# dsPIC.net
KiCad netlist of a schematic drawn in Altium Designer
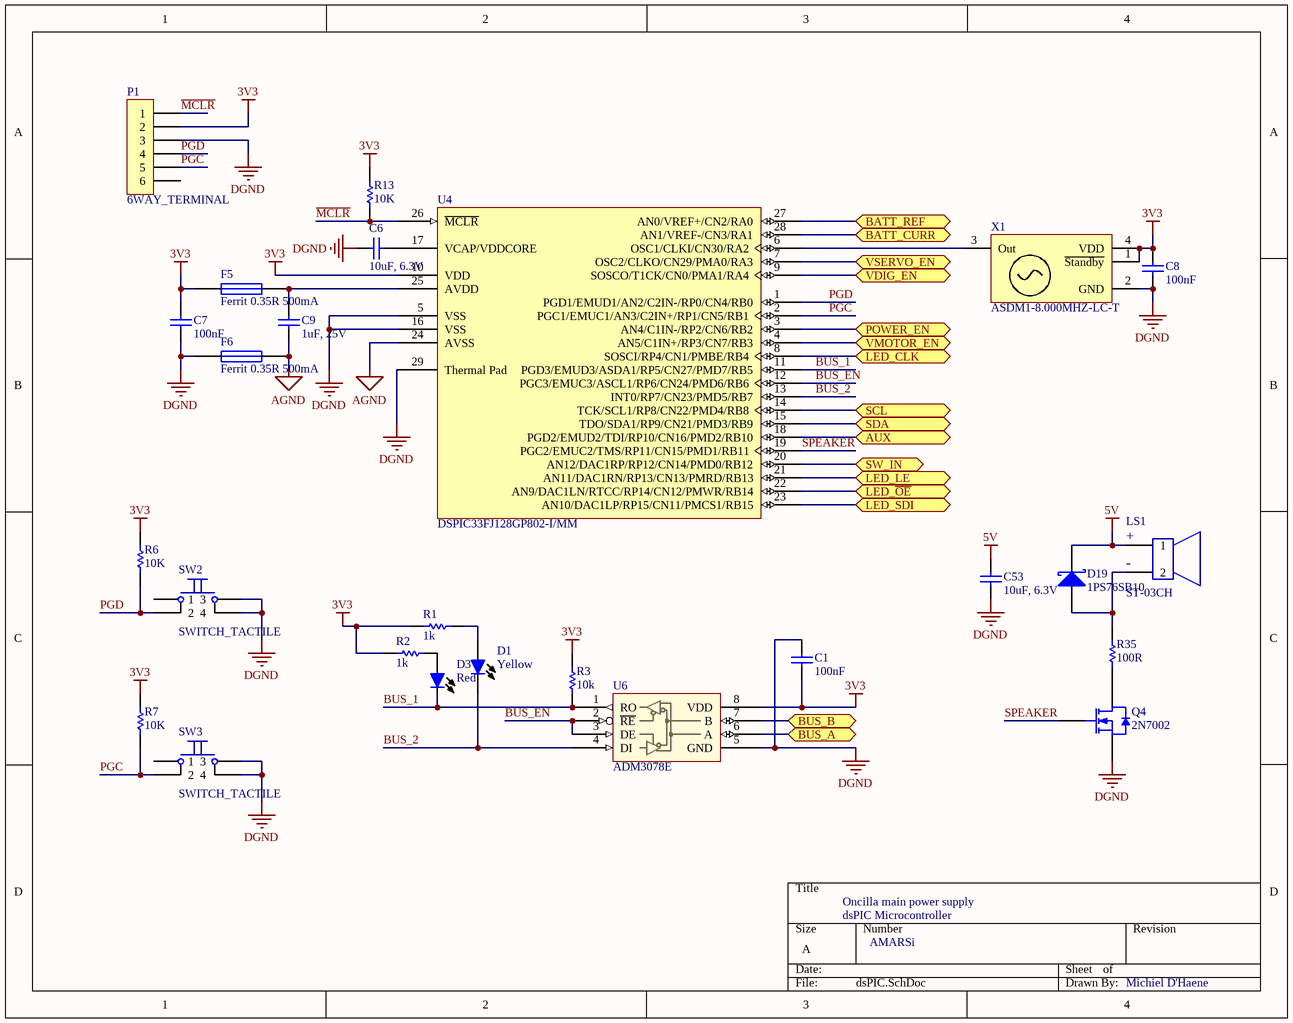
[diagram p0: dsPIC.SchDoc]

(export (version "E")
  (design (tool "Eeschema 10.0.6"))
  (components
    (comp (ref "C1")
      (value "100nF")
      (footprint "CAPC1608L")
      (description "Capacitor (Semiconductor SIM Model)")
      (fields (field (name "PUBLISHER") "Altium Limited"))
      (libsource (lib "Miscellaneous Devices") (part "Cap Semi"))
    )
    (comp (ref "C6")
      (value "10uF, 6.3V")
      (footprint "CAPC1608L")
      (description "Capacitor (Semiconductor SIM Model)")
      (fields (field (name "PUBLISHER") "Altium Limited"))
      (libsource (lib "Miscellaneous Devices") (part "Cap Semi"))
    )
    (comp (ref "C7")
      (value "100nF")
      (footprint "CAPC1608L")
      (description "Capacitor (Semiconductor SIM Model)")
      (fields (field (name "PUBLISHER") "Altium Limited"))
      (libsource (lib "Miscellaneous Devices") (part "Cap Semi"))
    )
    (comp (ref "C8")
      (value "100nF")
      (footprint "CAPC1608L")
      (description "Capacitor (Semiconductor SIM Model)")
      (fields (field (name "PUBLISHER") "Altium Limited"))
      (libsource (lib "Miscellaneous Devices") (part "Cap Semi"))
    )
    (comp (ref "C9")
      (value "1uF, 25V")
      (footprint "CAPC1608L")
      (description "Capacitor (Semiconductor SIM Model)")
      (fields (field (name "PUBLISHER") "Altium Limited"))
      (libsource (lib "Miscellaneous Devices") (part "Cap Semi"))
    )
    (comp (ref "C53")
      (value "10uF, 6.3V")
      (footprint "CAPC1608L")
      (description "Capacitor (Semiconductor SIM Model)")
      (fields (field (name "Comment") "1uF, 25V") (field (name "PUBLISHER") "Altium Limited"))
      (libsource (lib "Miscellaneous Devices") (part "Cap Semi"))
    )
    (comp (ref "D1")
      (value "LED Yellow")
      (footprint "CD1608-0603")
      (description "LED")
      (fields (field (name "COLOR") "Yellow"))
      (libsource (lib "Roombots") (part "LED"))
    )
    (comp (ref "D3")
      (value "LED Red")
      (footprint "CD1608-0603")
      (description "LED")
      (fields (field (name "COLOR") "Red"))
      (libsource (lib "Roombots") (part "LED"))
    )
    (comp (ref "D19")
      (value "1PS76SB10")
      (footprint "SOD323")
      (description "Schottky Barrier Diode")
      (fields (field (name "PUBLISHER") "Altium Limited"))
      (libsource (lib "Philips Discrete Diode - Schottky") (part "1PS76SB10"))
    )
    (comp (ref "F5")
      (value "Ferrit 0.35R 500mA")
      (footprint "RESC1608L")
      (description "Ferrit Bead")
      (fields (field (name "PUBLISHER") "Altium Limited"))
      (libsource (lib "Miscellaneous Devices") (part "Fuse 1"))
    )
    (comp (ref "F6")
      (value "Ferrit 0.35R 500mA")
      (footprint "RESC1608L")
      (description "Ferrit Bead")
      (fields (field (name "PUBLISHER") "Altium Limited"))
      (libsource (lib "Miscellaneous Devices") (part "Fuse 1"))
    )
    (comp (ref "LS1")
      (value "ST-03CH")
      (footprint "PIEZO_8.5x8.5MM")
      (libsource (lib "New_library") (part "piezo_sounder"))
    )
    (comp (ref "P1")
      (value "6WAY_TERMINAL")
      (footprint "MICROMATCH_6WAY_SE")
      (libsource (lib "New_library") (part "6WAY_TERMINAL"))
    )
    (comp (ref "Q4")
      (value "2N7002")
      (footprint "SOT23_N")
      (description "N-channel Enhancement Mode Field-effect Transistor")
      (fields (field (name "PUBLISHER") "Altium Limited"))
      (libsource (lib "Philips Discrete MOSFET - Low Power") (part "BST82"))
    )
    (comp (ref "R1")
      (value "1k")
      (footprint "RESC1608L")
      (description "Semiconductor Resistor")
      (fields (field (name "PUBLISHER") "Altium Limited"))
      (libsource (lib "Miscellaneous Devices") (part "Res Semi"))
    )
    (comp (ref "R2")
      (value "1k")
      (footprint "RESC1608L")
      (description "Semiconductor Resistor")
      (fields (field (name "PUBLISHER") "Altium Limited"))
      (libsource (lib "Miscellaneous Devices") (part "Res Semi"))
    )
    (comp (ref "R3")
      (value "10k")
      (footprint "RESC1608L")
      (description "Semiconductor Resistor")
      (fields (field (name "PUBLISHER") "Altium Limited"))
      (libsource (lib "Miscellaneous Devices") (part "Res Semi"))
    )
    (comp (ref "R6")
      (value "10K")
      (footprint "RESC1608L")
      (description "Semiconductor Resistor")
      (fields (field (name "Comment") "10k") (field (name "PUBLISHER") "Altium Limited"))
      (libsource (lib "Miscellaneous Devices") (part "Res Semi"))
    )
    (comp (ref "R7")
      (value "10K")
      (footprint "RESC1608L")
      (description "Semiconductor Resistor")
      (fields (field (name "Comment") "10k") (field (name "PUBLISHER") "Altium Limited"))
      (libsource (lib "Miscellaneous Devices") (part "Res Semi"))
    )
    (comp (ref "R13")
      (value "10K")
      (footprint "RESC1608L")
      (description "Semiconductor Resistor")
      (fields (field (name "Comment") "10k") (field (name "PUBLISHER") "Altium Limited"))
      (libsource (lib "Miscellaneous Devices") (part "Res Semi"))
    )
    (comp (ref "R35")
      (value "100R")
      (footprint "RESC2012L")
      (description "Semiconductor Resistor")
      (fields (field (name "PUBLISHER") "Altium Limited"))
      (libsource (lib "Miscellaneous Devices") (part "Res Semi"))
    )
    (comp (ref "SW2")
      (value "SWITCH_TACTILE")
      (footprint "TACTILE_SWITCH")
      (libsource (lib "New_library") (part "SWITCH_TACTILE"))
    )
    (comp (ref "SW3")
      (value "SWITCH_TACTILE")
      (footprint "TACTILE_SWITCH")
      (libsource (lib "New_library") (part "SWITCH_TACTILE"))
    )
    (comp (ref "U4")
      (value "DSPIC33FJ128GP802-I/MM")
      (footprint "QFNS-MM28_N")
      (fields (field (name "PUBLISHER") "Altium Limited"))
      (libsource (lib "Microchip DSC 16-Bit dsPIC33F") (part "DSPIC33FJ128GP802T-I/MM"))
    )
    (comp (ref "U6")
      (value "ADM3078E")
      (footprint "SOIC-8_M")
      (description "Half-Duplex RS485 Transciever, 3.3V, 16Mbps")
      (libsource (lib "Roombots") (part "ADM3078E"))
    )
    (comp (ref "X1")
      (value "ASDM1-8.000MHZ-LC-T")
      (footprint "Crystal-Oscillator-2520")
      (description "Oscillator")
      (libsource (lib "Roombots") (part "Oscillator"))
    )
  )
  (nets
    (net (code "1") (name "/AUX") (class "Default")
      (node (ref "U4") (pin "18") (pinfunction "PGD2/EMUD2/TDI/RP10/CN16/PMD2/RB10_18") (pintype "bidirectional"))
    )
    (net (code "2") (name "/BATT_CURR") (class "Default")
      (node (ref "U4") (pin "28") (pinfunction "AN1/VREF-/CN3/RA1_28") (pintype "bidirectional"))
    )
    (net (code "3") (name "/BATT_REF") (class "Default")
      (node (ref "U4") (pin "27") (pinfunction "AN0/VREF+/CN2/RA0_27") (pintype "bidirectional"))
    )
    (net (code "4") (name "/BUS_1") (class "Default")
      (node (ref "D3") (pin "2") (pinfunction "C_2") (pintype "passive"))
      (node (ref "R3") (pin "1") (pinfunction "1_1") (pintype "passive"))
      (node (ref "U4") (pin "11") (pinfunction "PGD3/EMUD3/ASDA1/RP5/CN27/PMD7/RB5_11") (pintype "bidirectional"))
      (node (ref "U6") (pin "1") (pinfunction "RO_1") (pintype "output"))
    )
    (net (code "5") (name "/BUS_2") (class "Default")
      (node (ref "D1") (pin "2") (pinfunction "C_2") (pintype "passive"))
      (node (ref "U4") (pin "13") (pinfunction "INT0/RP7/CN23/PMD5/RB7_13") (pintype "bidirectional"))
      (node (ref "U6") (pin "4") (pinfunction "DI_4") (pintype "input"))
    )
    (net (code "6") (name "/BUS_A") (class "Default")
      (node (ref "U6") (pin "6") (pinfunction "A_6") (pintype "bidirectional"))
    )
    (net (code "7") (name "/BUS_B") (class "Default")
      (node (ref "U6") (pin "7") (pinfunction "B_7") (pintype "bidirectional"))
    )
    (net (code "8") (name "/BUS_EN") (class "Default")
      (node (ref "U4") (pin "12") (pinfunction "PGC3/EMUC3/ASCL1/RP6/CN24/PMD6/RB6_12") (pintype "bidirectional"))
      (node (ref "U6") (pin "2") (pinfunction "~{RE}_2") (pintype "input"))
      (node (ref "U6") (pin "3") (pinfunction "DE_3") (pintype "input"))
    )
    (net (code "9") (name "/LED_CLK") (class "Default")
      (node (ref "U4") (pin "8") (pinfunction "SOSCI/RP4/CN1/PMBE/RB4_8") (pintype "bidirectional"))
    )
    (net (code "10") (name "/LED_LE") (class "Default")
      (node (ref "U4") (pin "21") (pinfunction "AN11/DAC1RN/RP13/CN13/PMRD/RB13_21") (pintype "bidirectional"))
    )
    (net (code "11") (name "/LED_SDI") (class "Default")
      (node (ref "U4") (pin "23") (pinfunction "AN10/DAC1LP/RP15/CN11/PMCS1/RB15_23") (pintype "bidirectional"))
    )
    (net (code "12") (name "/LED_~{OE}") (class "Default")
      (node (ref "U4") (pin "22") (pinfunction "AN9/DAC1LN/RTCC/RP14/CN12/PMWR/RB14_22") (pintype "bidirectional"))
    )
    (net (code "13") (name "/PGC") (class "Default")
      (node (ref "P1") (pin "5") (pinfunction "5_5") (pintype "passive"))
      (node (ref "R7") (pin "1") (pinfunction "1_1") (pintype "passive"))
      (node (ref "SW3") (pin "2") (pinfunction "2_2") (pintype "passive"))
      (node (ref "U4") (pin "2") (pinfunction "PGC1/EMUC1/AN3/C2IN+/RP1/CN5/RB1_2") (pintype "bidirectional"))
    )
    (net (code "14") (name "/PGD") (class "Default")
      (node (ref "P1") (pin "4") (pinfunction "4_4") (pintype "passive"))
      (node (ref "R6") (pin "1") (pinfunction "1_1") (pintype "passive"))
      (node (ref "SW2") (pin "2") (pinfunction "2_2") (pintype "passive"))
      (node (ref "U4") (pin "1") (pinfunction "PGD1/EMUD1/AN2/C2IN-/RP0/CN4/RB0_1") (pintype "bidirectional"))
    )
    (net (code "15") (name "/POWER_EN") (class "Default")
      (node (ref "U4") (pin "3") (pinfunction "AN4/C1IN-/RP2/CN6/RB2_3") (pintype "bidirectional"))
    )
    (net (code "16") (name "/SCL") (class "Default")
      (node (ref "U4") (pin "14") (pinfunction "TCK/SCL1/RP8/CN22/PMD4/RB8_14") (pintype "bidirectional"))
    )
    (net (code "17") (name "/SDA") (class "Default")
      (node (ref "U4") (pin "15") (pinfunction "TDO/SDA1/RP9/CN21/PMD3/RB9_15") (pintype "bidirectional"))
    )
    (net (code "18") (name "/SPEAKER") (class "Default")
      (node (ref "Q4") (pin "1") (pinfunction "G_1") (pintype "passive"))
      (node (ref "U4") (pin "19") (pinfunction "PGC2/EMUC2/TMS/RP11/CN15/PMD1/RB11_19") (pintype "bidirectional"))
    )
    (net (code "19") (name "/SW_IN") (class "Default")
      (node (ref "U4") (pin "20") (pinfunction "AN12/DAC1RP/RP12/CN14/PMD0/RB12_20") (pintype "bidirectional"))
    )
    (net (code "20") (name "/VDIG_EN") (class "Default")
      (node (ref "U4") (pin "9") (pinfunction "SOSCO/T1CK/CN0/PMA1/RA4_9") (pintype "bidirectional"))
    )
    (net (code "21") (name "/VMOTOR_EN") (class "Default")
      (node (ref "U4") (pin "4") (pinfunction "AN5/C1IN+/RP3/CN7/RB3_4") (pintype "bidirectional"))
    )
    (net (code "22") (name "/VSERVO_EN") (class "Default")
      (node (ref "U4") (pin "7") (pinfunction "OSC2/CLKO/CN29/PMA0/RA3_7") (pintype "bidirectional"))
    )
    (net (code "23") (name "/~{MCLR}") (class "Default")
      (node (ref "P1") (pin "1") (pinfunction "1_1") (pintype "passive"))
      (node (ref "R13") (pin "1") (pinfunction "1_1") (pintype "passive"))
      (node (ref "U4") (pin "26") (pinfunction "~{MCLR}_26") (pintype "input"))
    )
    (net (code "24") (name "3V3") (class "Default")
      (node (ref "C1") (pin "1") (pinfunction "1_1") (pintype "passive"))
      (node (ref "C7") (pin "2") (pinfunction "2_2") (pintype "passive"))
      (node (ref "C8") (pin "2") (pinfunction "2_2") (pintype "passive"))
      (node (ref "F5") (pin "1") (pinfunction "1_1") (pintype "passive"))
      (node (ref "P1") (pin "2") (pinfunction "2_2") (pintype "passive"))
      (node (ref "R1") (pin "1") (pinfunction "1_1") (pintype "passive"))
      (node (ref "R13") (pin "2") (pinfunction "2_2") (pintype "passive"))
      (node (ref "R2") (pin "1") (pinfunction "1_1") (pintype "passive"))
      (node (ref "R3") (pin "2") (pinfunction "2_2") (pintype "passive"))
      (node (ref "R6") (pin "2") (pinfunction "2_2") (pintype "passive"))
      (node (ref "R7") (pin "2") (pinfunction "2_2") (pintype "passive"))
      (node (ref "U4") (pin "10") (pinfunction "VDD_10") (pintype "power_in"))
      (node (ref "U6") (pin "8") (pinfunction "VDD_8") (pintype "power_in"))
      (node (ref "X1") (pin "1") (pinfunction "~{Standby}_1") (pintype "passive"))
      (node (ref "X1") (pin "4") (pinfunction "VDD_4") (pintype "passive"))
    )
    (net (code "25") (name "5V") (class "Default")
      (node (ref "C53") (pin "1") (pinfunction "1_1") (pintype "passive"))
      (node (ref "D19") (pin "1") (pinfunction "K_1") (pintype "passive"))
      (node (ref "LS1") (pin "1") (pinfunction "1_1") (pintype "passive"))
    )
    (net (code "26") (name "AGND") (class "Default")
      (node (ref "C9") (pin "1") (pinfunction "1_1") (pintype "passive"))
      (node (ref "F6") (pin "2") (pinfunction "2_2") (pintype "passive"))
      (node (ref "U4") (pin "24") (pinfunction "AVSS_24") (pintype "power_in"))
    )
    (net (code "27") (name "DGND") (class "Default")
      (node (ref "C1") (pin "2") (pinfunction "2_2") (pintype "passive"))
      (node (ref "C53") (pin "2") (pinfunction "2_2") (pintype "passive"))
      (node (ref "C6") (pin "1") (pinfunction "1_1") (pintype "passive"))
      (node (ref "C7") (pin "1") (pinfunction "1_1") (pintype "passive"))
      (node (ref "C8") (pin "1") (pinfunction "1_1") (pintype "passive"))
      (node (ref "F6") (pin "1") (pinfunction "1_1") (pintype "passive"))
      (node (ref "P1") (pin "3") (pinfunction "3_3") (pintype "passive"))
      (node (ref "Q4") (pin "2") (pinfunction "S_2") (pintype "passive"))
      (node (ref "SW2") (pin "3") (pinfunction "3_3") (pintype "passive"))
      (node (ref "SW2") (pin "4") (pinfunction "4_4") (pintype "passive"))
      (node (ref "SW3") (pin "3") (pinfunction "3_3") (pintype "passive"))
      (node (ref "SW3") (pin "4") (pinfunction "4_4") (pintype "passive"))
      (node (ref "U4") (pin "16") (pinfunction "VSS_16") (pintype "power_in"))
      (node (ref "U4") (pin "29") (pinfunction "Thermal_Pad_29") (pintype "passive"))
      (node (ref "U4") (pin "5") (pinfunction "VSS_5") (pintype "power_in"))
      (node (ref "U6") (pin "5") (pinfunction "GND_5") (pintype "power_in"))
      (node (ref "X1") (pin "2") (pinfunction "GND_2") (pintype "passive"))
    )
    (net (code "28") (name "Net-(D1-A)") (class "Default")
      (node (ref "D1") (pin "1") (pinfunction "A_1") (pintype "passive"))
      (node (ref "R1") (pin "2") (pinfunction "2_2") (pintype "passive"))
    )
    (net (code "29") (name "Net-(D3-A)") (class "Default")
      (node (ref "D3") (pin "1") (pinfunction "A_1") (pintype "passive"))
      (node (ref "R2") (pin "2") (pinfunction "2_2") (pintype "passive"))
    )
    (net (code "30") (name "Net-(D19-A)") (class "Default")
      (node (ref "D19") (pin "2") (pinfunction "A_2") (pintype "passive"))
      (node (ref "LS1") (pin "2") (pinfunction "2_2") (pintype "passive"))
      (node (ref "R35") (pin "1") (pinfunction "1_1") (pintype "passive"))
    )
    (net (code "31") (name "Net-(Q4-D)") (class "Default")
      (node (ref "Q4") (pin "3") (pinfunction "D_3") (pintype "passive"))
      (node (ref "R35") (pin "2") (pinfunction "2_2") (pintype "passive"))
    )
    (net (code "32") (name "Net-(U4-AVDD)") (class "Default")
      (node (ref "C9") (pin "2") (pinfunction "2_2") (pintype "passive"))
      (node (ref "F5") (pin "2") (pinfunction "2_2") (pintype "passive"))
      (node (ref "U4") (pin "25") (pinfunction "AVDD_25") (pintype "power_in"))
    )
    (net (code "33") (name "Net-(U4-OSC1{slash}CLKI{slash}CN30{slash}RA2)") (class "Default")
      (node (ref "U4") (pin "6") (pinfunction "OSC1/CLKI/CN30/RA2_6") (pintype "bidirectional"))
      (node (ref "X1") (pin "3") (pinfunction "Out_3") (pintype "passive"))
    )
    (net (code "34") (name "Net-(U4-VCAP{slash}VDDCORE)") (class "Default")
      (node (ref "C6") (pin "2") (pinfunction "2_2") (pintype "passive"))
      (node (ref "U4") (pin "17") (pinfunction "VCAP/VDDCORE_17") (pintype "power_in"))
    )
    (net (code "35") (name "unconnected-(P1-Pad6)") (class "Default")
      (node (ref "P1") (pin "6") (pinfunction "6_6") (pintype "passive"))
    )
    (net (code "36") (name "unconnected-(SW2-Pad1)") (class "Default")
      (node (ref "SW2") (pin "1") (pinfunction "1_1") (pintype "passive"))
    )
    (net (code "37") (name "unconnected-(SW3-Pad1)") (class "Default")
      (node (ref "SW3") (pin "1") (pinfunction "1_1") (pintype "passive"))
    )
  )
)
